# SDCard.net
KiCad netlist of a schematic drawn in Altium Designer
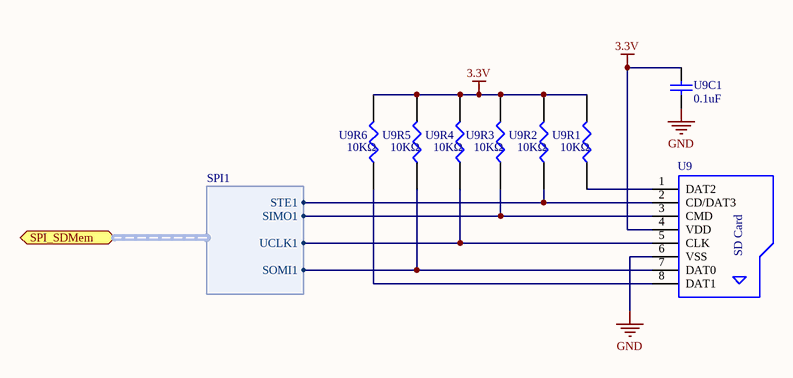
[diagram p0: SDCard.SchDoc]

(export (version "E")
  (design (tool "Eeschema 10.0.6"))
  (components
    (comp (ref "U9")
      (value "WE-Card Connectors 693072010801")
      (footprint "693072010801")
      (description "WR-CRD Micro SD_Hinge / CONN MICRO SD CARD HINGED TYPE")
      (fields
        (field (name "MANUFACTURER") "Würth Elektronik")
        (field (name "MANUFACTURER PART NUMBER") "693072010801")
      )
      (libsource (lib "ALTIUM-693072010801-rev16b") (part "WE-Card Connectors 693072010801"))
    )
    (comp (ref "U9C1")
      (value "0.1uF")
      (footprint "0603 - CAP")
      (description "CAP CERAMIC 0.1UF, 25V, X7R, 0603")
      (fields
        (field (name "MANUFACTURER PART NUMBER") "CGJ3E2X7R1E104K080AA")
        (field (name "MANUFACTURER") "TDK Corporation")
      )
      (libsource (lib "*") (part "Cap"))
    )
    (comp (ref "U9R1")
      (value "10KΩ")
      (footprint "0805-RES")
      (description "10 kOhms ±5% 0.125W, 1/8W Chip Resistor 0805")
      (fields
        (field (name "MANUFACTURER PART NUMBER") "RC0805JR-0710KL")
        (field (name "MANUFACTURER") "Yageo")
      )
      (libsource (lib "*") (part "RES1"))
    )
    (comp (ref "U9R2")
      (value "10KΩ")
      (footprint "0805-RES")
      (description "10 kOhms ±5% 0.125W, 1/8W Chip Resistor 0805")
      (fields
        (field (name "MANUFACTURER PART NUMBER") "RC0805JR-0710KL")
        (field (name "MANUFACTURER") "Yageo")
      )
      (libsource (lib "*") (part "RES1"))
    )
    (comp (ref "U9R3")
      (value "10KΩ")
      (footprint "0805-RES")
      (description "10 kOhms ±5% 0.125W, 1/8W Chip Resistor 0805")
      (fields
        (field (name "MANUFACTURER PART NUMBER") "RC0805JR-0710KL")
        (field (name "MANUFACTURER") "Yageo")
      )
      (libsource (lib "*") (part "RES1"))
    )
    (comp (ref "U9R4")
      (value "10KΩ")
      (footprint "0805-RES")
      (description "10 kOhms ±5% 0.125W, 1/8W Chip Resistor 0805")
      (fields
        (field (name "MANUFACTURER PART NUMBER") "RC0805JR-0710KL")
        (field (name "MANUFACTURER") "Yageo")
      )
      (libsource (lib "*") (part "RES1"))
    )
    (comp (ref "U9R5")
      (value "10KΩ")
      (footprint "0805-RES")
      (description "10 kOhms ±5% 0.125W, 1/8W Chip Resistor 0805")
      (fields
        (field (name "MANUFACTURER PART NUMBER") "RC0805JR-0710KL")
        (field (name "MANUFACTURER") "Yageo")
      )
      (libsource (lib "*") (part "RES1"))
    )
    (comp (ref "U9R6")
      (value "10KΩ")
      (footprint "0805-RES")
      (description "10 kOhms ±5% 0.125W, 1/8W Chip Resistor 0805")
      (fields
        (field (name "MANUFACTURER PART NUMBER") "RC0805JR-0710KL")
        (field (name "MANUFACTURER") "Yageo")
      )
      (libsource (lib "*") (part "RES1"))
    )
  )
  (nets
    (net (code "3") (name "3.3V") (class "Default")
      (node (ref "U9") (pin "4") (pinfunction "VDD_4") (pintype "passive"))
      (node (ref "U9C1") (pin "1") (pinfunction "1_1") (pintype "passive"))
      (node (ref "U9R1") (pin "2") (pinfunction "2_2") (pintype "passive"))
      (node (ref "U9R2") (pin "2") (pinfunction "2_2") (pintype "passive"))
      (node (ref "U9R3") (pin "2") (pinfunction "2_2") (pintype "passive"))
      (node (ref "U9R4") (pin "2") (pinfunction "2_2") (pintype "passive"))
      (node (ref "U9R5") (pin "2") (pinfunction "2_2") (pintype "passive"))
      (node (ref "U9R6") (pin "2") (pinfunction "2_2") (pintype "passive"))
    )
    (net (code "4") (name "GND") (class "Default")
      (node (ref "U9") (pin "6") (pinfunction "VSS_6") (pintype "passive"))
      (node (ref "U9C1") (pin "2") (pinfunction "2_2") (pintype "passive"))
    )
    (net (code "5") (name "Net-(U9-CD{slash}DAT3)") (class "Default")
      (node (ref "U9") (pin "2") (pinfunction "CD/DAT3_2") (pintype "passive"))
      (node (ref "U9R2") (pin "1") (pinfunction "1_1") (pintype "passive"))
    )
    (net (code "6") (name "Net-(U9-CLK)") (class "Default")
      (node (ref "U9") (pin "5") (pinfunction "CLK_5") (pintype "passive"))
      (node (ref "U9R4") (pin "1") (pinfunction "1_1") (pintype "passive"))
    )
    (net (code "7") (name "Net-(U9-CMD)") (class "Default")
      (node (ref "U9") (pin "3") (pinfunction "CMD_3") (pintype "passive"))
      (node (ref "U9R3") (pin "1") (pinfunction "1_1") (pintype "passive"))
    )
    (net (code "8") (name "Net-(U9-DAT0)") (class "Default")
      (node (ref "U9") (pin "7") (pinfunction "DAT0_7") (pintype "passive"))
      (node (ref "U9R5") (pin "1") (pinfunction "1_1") (pintype "passive"))
    )
    (net (code "9") (name "Net-(U9-DAT1)") (class "Default")
      (node (ref "U9") (pin "8") (pinfunction "DAT1_8") (pintype "passive"))
      (node (ref "U9R6") (pin "1") (pinfunction "1_1") (pintype "passive"))
    )
    (net (code "10") (name "Net-(U9-DAT2)") (class "Default")
      (node (ref "U9") (pin "1") (pinfunction "DAT2_1") (pintype "passive"))
      (node (ref "U9R1") (pin "1") (pinfunction "1_1") (pintype "passive"))
    )
  )
)
